# OneSLiPoCharger.net
KiCad netlist of a schematic drawn in EAGLE
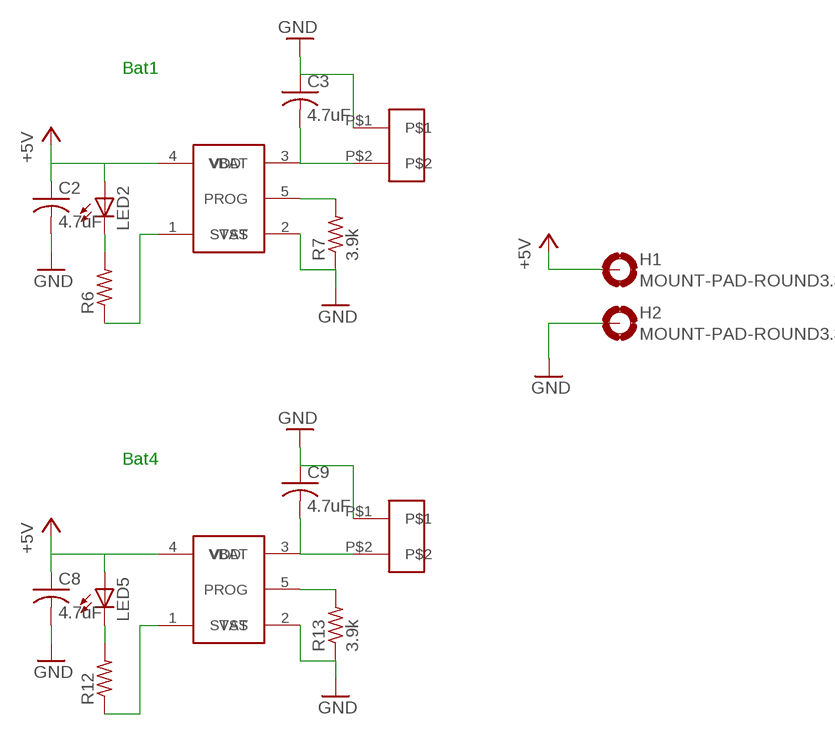
[diagram p0: schematic, sheet 1]

(export (version "E")
  (design (tool "Eeschema 10.0.6"))
  (components
    (comp (ref "C2")
      (value "4.7uF")
      (footprint "eagle-import:C0805")
      (libsource (lib "eagle-import") (part "C-USC0805"))
    )
    (comp (ref "C3")
      (value "4.7uF")
      (footprint "eagle-import:C0805")
      (libsource (lib "eagle-import") (part "C-USC0805"))
    )
    (comp (ref "C8")
      (value "4.7uF")
      (footprint "eagle-import:C0805")
      (libsource (lib "eagle-import") (part "C-USC0805"))
    )
    (comp (ref "C9")
      (value "4.7uF")
      (footprint "eagle-import:C0805")
      (libsource (lib "eagle-import") (part "C-USC0805"))
    )
    (comp (ref "H1")
      (value "MOUNT-PAD-ROUND3.3")
      (footprint "eagle-import:3,3-PAD")
      (libsource (lib "eagle-import") (part "MOUNT-PAD-ROUND3.3"))
    )
    (comp (ref "H2")
      (value "MOUNT-PAD-ROUND3.3")
      (footprint "eagle-import:3,3-PAD")
      (libsource (lib "eagle-import") (part "MOUNT-PAD-ROUND3.3"))
    )
    (comp (ref "LED2")
      (value "LED3MM")
      (footprint "eagle-import:LED3MM")
      (libsource (lib "eagle-import") (part "LED3MM"))
    )
    (comp (ref "LED5")
      (value "LED3MM")
      (footprint "eagle-import:LED3MM")
      (libsource (lib "eagle-import") (part "LED3MM"))
    )
    (comp (ref "R6")
      (value "R-US_M0805")
      (footprint "eagle-import:M0805")
      (libsource (lib "eagle-import") (part "R-US_M0805"))
    )
    (comp (ref "R7")
      (value "3.9k")
      (footprint "eagle-import:M0805")
      (libsource (lib "eagle-import") (part "R-US_M0805"))
    )
    (comp (ref "R12")
      (value "R-US_M0805")
      (footprint "eagle-import:M0805")
      (libsource (lib "eagle-import") (part "R-US_M0805"))
    )
    (comp (ref "R13")
      (value "3.9k")
      (footprint "eagle-import:M0805")
      (libsource (lib "eagle-import") (part "R-US_M0805"))
    )
    (comp (ref "U$1")
      (value "MCP73831")
      (footprint "eagle-import:MCP73831-SOT23")
      (libsource (lib "eagle-import") (part "MCP73831"))
    )
    (comp (ref "U$2")
      (value "PICOBLADE-2PIN")
      (footprint "eagle-import:PICOBLADE-2PIN")
      (libsource (lib "eagle-import") (part "PICOBLADE-2PIN"))
    )
    (comp (ref "U$8")
      (value "MCP73831")
      (footprint "eagle-import:MCP73831-SOT23")
      (libsource (lib "eagle-import") (part "MCP73831"))
    )
    (comp (ref "U$9")
      (value "PICOBLADE-2PIN")
      (footprint "eagle-import:PICOBLADE-2PIN")
      (libsource (lib "eagle-import") (part "PICOBLADE-2PIN"))
    )
  )
  (nets
    (net (code "1") (name "+5V") (class "Default")
      (node (ref "C2") (pin "1") (pinfunction "1_1") (pintype "passive"))
      (node (ref "C8") (pin "1") (pinfunction "1_1") (pintype "passive"))
      (node (ref "H1") (pin "B3,3") (pinfunction "MOUNT_B3,3") (pintype "passive"))
      (node (ref "LED2") (pin "A") (pinfunction "A_A") (pintype "passive"))
      (node (ref "LED5") (pin "A") (pinfunction "A_A") (pintype "passive"))
      (node (ref "U$1") (pin "4") (pinfunction "VDD_4") (pintype "bidirectional"))
      (node (ref "U$8") (pin "4") (pinfunction "VDD_4") (pintype "bidirectional"))
    )
    (net (code "2") (name "GND") (class "Default")
      (node (ref "C2") (pin "2") (pinfunction "2_2") (pintype "passive"))
      (node (ref "C3") (pin "1") (pinfunction "1_1") (pintype "passive"))
      (node (ref "C8") (pin "2") (pinfunction "2_2") (pintype "passive"))
      (node (ref "C9") (pin "1") (pinfunction "1_1") (pintype "passive"))
      (node (ref "H2") (pin "B3,3") (pinfunction "MOUNT_B3,3") (pintype "passive"))
      (node (ref "R13") (pin "1") (pinfunction "1_1") (pintype "passive"))
      (node (ref "R7") (pin "1") (pinfunction "1_1") (pintype "passive"))
      (node (ref "U$1") (pin "2") (pinfunction "VSS_2") (pintype "bidirectional"))
      (node (ref "U$2") (pin "P$1") (pinfunction "P$1_P$1") (pintype "bidirectional"))
      (node (ref "U$8") (pin "2") (pinfunction "VSS_2") (pintype "bidirectional"))
      (node (ref "U$9") (pin "P$1") (pinfunction "P$1_P$1") (pintype "bidirectional"))
    )
    (net (code "3") (name "Net-(LED2-C)") (class "Default")
      (node (ref "LED2") (pin "K") (pinfunction "C_K") (pintype "passive"))
      (node (ref "R6") (pin "2") (pinfunction "2_2") (pintype "passive"))
    )
    (net (code "4") (name "Net-(LED5-C)") (class "Default")
      (node (ref "LED5") (pin "K") (pinfunction "C_K") (pintype "passive"))
      (node (ref "R12") (pin "2") (pinfunction "2_2") (pintype "passive"))
    )
    (net (code "5") (name "Net-(U$1-PROG)") (class "Default")
      (node (ref "R7") (pin "2") (pinfunction "2_2") (pintype "passive"))
      (node (ref "U$1") (pin "5") (pinfunction "PROG_5") (pintype "bidirectional"))
    )
    (net (code "6") (name "Net-(U$1-STAT)") (class "Default")
      (node (ref "R6") (pin "1") (pinfunction "1_1") (pintype "passive"))
      (node (ref "U$1") (pin "1") (pinfunction "STAT_1") (pintype "bidirectional"))
    )
    (net (code "7") (name "Net-(U$1-VBAT)") (class "Default")
      (node (ref "C3") (pin "2") (pinfunction "2_2") (pintype "passive"))
      (node (ref "U$1") (pin "3") (pinfunction "VBAT_3") (pintype "bidirectional"))
      (node (ref "U$2") (pin "P$2") (pinfunction "P$2_P$2") (pintype "bidirectional"))
    )
    (net (code "8") (name "Net-(U$8-PROG)") (class "Default")
      (node (ref "R13") (pin "2") (pinfunction "2_2") (pintype "passive"))
      (node (ref "U$8") (pin "5") (pinfunction "PROG_5") (pintype "bidirectional"))
    )
    (net (code "9") (name "Net-(U$8-STAT)") (class "Default")
      (node (ref "R12") (pin "1") (pinfunction "1_1") (pintype "passive"))
      (node (ref "U$8") (pin "1") (pinfunction "STAT_1") (pintype "bidirectional"))
    )
    (net (code "10") (name "Net-(U$8-VBAT)") (class "Default")
      (node (ref "C9") (pin "2") (pinfunction "2_2") (pintype "passive"))
      (node (ref "U$8") (pin "3") (pinfunction "VBAT_3") (pintype "bidirectional"))
      (node (ref "U$9") (pin "P$2") (pinfunction "P$2_P$2") (pintype "bidirectional"))
    )
  )
)
